# Rocky_Switch_SSR.net
KiCad netlist of a schematic drawn in EAGLE
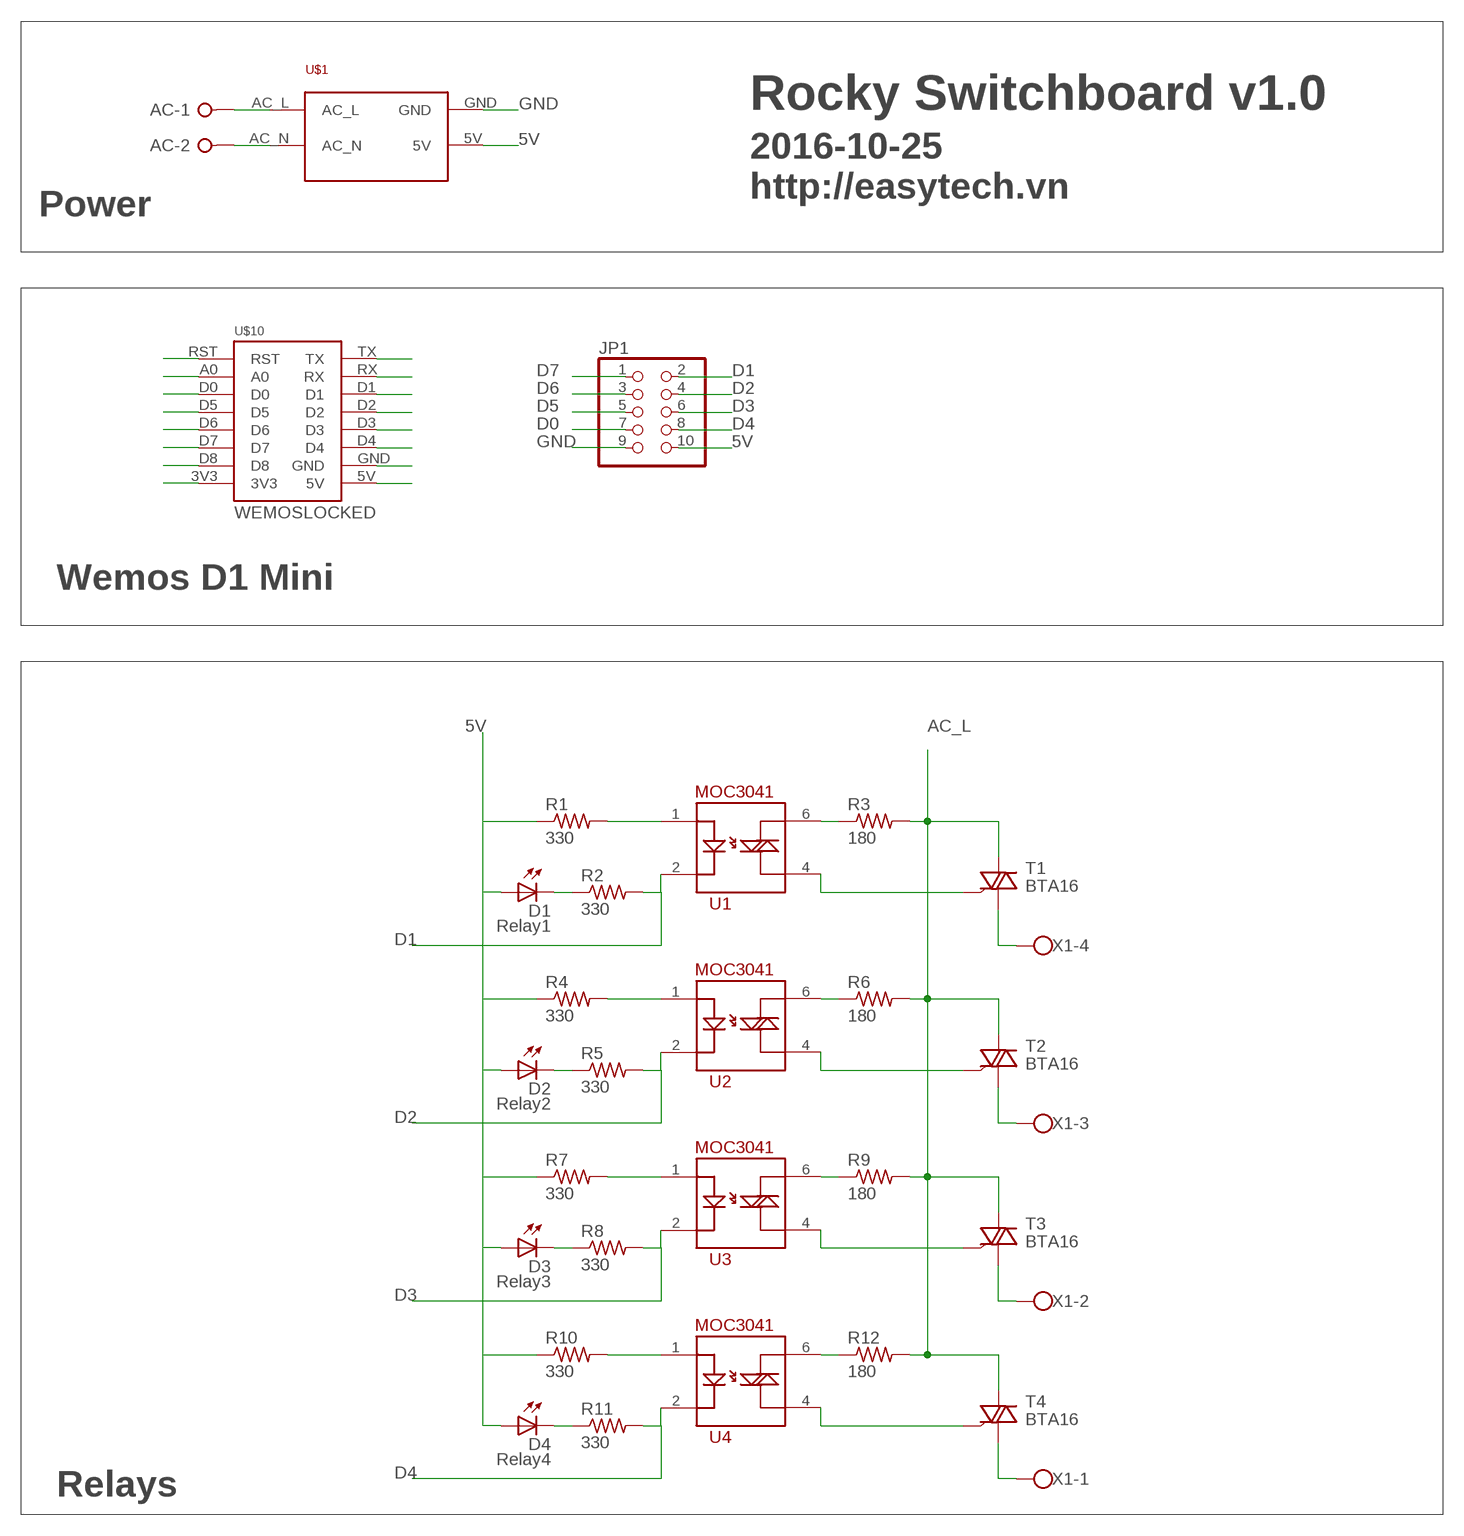
[diagram p0: schematic, sheet 1]

(export (version "E")
  (design (tool "Eeschema 10.0.6"))
  (components
    (comp (ref "AC")
      (value "W237-02P")
      (footprint "eagle-import:W237-132")
      (libsource (lib "eagle-import") (part "W237-02P"))
    )
    (comp (ref "D1")
      (value "Relay1")
      (footprint "eagle-import:CHIP-LED0805")
      (libsource (lib "eagle-import") (part "LEDCHIP-LED0805"))
    )
    (comp (ref "D2")
      (value "Relay2")
      (footprint "eagle-import:CHIP-LED0805")
      (libsource (lib "eagle-import") (part "LEDCHIP-LED0805"))
    )
    (comp (ref "D3")
      (value "Relay3")
      (footprint "eagle-import:CHIP-LED0805")
      (libsource (lib "eagle-import") (part "LEDCHIP-LED0805"))
    )
    (comp (ref "D4")
      (value "Relay4")
      (footprint "eagle-import:CHIP-LED0805")
      (libsource (lib "eagle-import") (part "LEDCHIP-LED0805"))
    )
    (comp (ref "JP1")
      (value "PINHD-2X5")
      (footprint "eagle-import:2X05")
      (libsource (lib "eagle-import") (part "PINHD-2X5"))
    )
    (comp (ref "R1")
      (value "330")
      (footprint "eagle-import:R0805")
      (libsource (lib "eagle-import") (part "R-US_R0805"))
    )
    (comp (ref "R2")
      (value "330")
      (footprint "eagle-import:R0805")
      (libsource (lib "eagle-import") (part "R-US_R0805"))
    )
    (comp (ref "R3")
      (value "180")
      (footprint "eagle-import:0204_7")
      (libsource (lib "eagle-import") (part "R-US_0204/7"))
    )
    (comp (ref "R4")
      (value "330")
      (footprint "eagle-import:R0805")
      (libsource (lib "eagle-import") (part "R-US_R0805"))
    )
    (comp (ref "R5")
      (value "330")
      (footprint "eagle-import:R0805")
      (libsource (lib "eagle-import") (part "R-US_R0805"))
    )
    (comp (ref "R6")
      (value "180")
      (footprint "eagle-import:0204_7")
      (libsource (lib "eagle-import") (part "R-US_0204/7"))
    )
    (comp (ref "R7")
      (value "330")
      (footprint "eagle-import:R0805")
      (libsource (lib "eagle-import") (part "R-US_R0805"))
    )
    (comp (ref "R8")
      (value "330")
      (footprint "eagle-import:R0805")
      (libsource (lib "eagle-import") (part "R-US_R0805"))
    )
    (comp (ref "R9")
      (value "180")
      (footprint "eagle-import:0204_7")
      (libsource (lib "eagle-import") (part "R-US_0204/7"))
    )
    (comp (ref "R10")
      (value "330")
      (footprint "eagle-import:R0805")
      (libsource (lib "eagle-import") (part "R-US_R0805"))
    )
    (comp (ref "R11")
      (value "330")
      (footprint "eagle-import:R0805")
      (libsource (lib "eagle-import") (part "R-US_R0805"))
    )
    (comp (ref "R12")
      (value "180")
      (footprint "eagle-import:0204_7")
      (libsource (lib "eagle-import") (part "R-US_0204/7"))
    )
    (comp (ref "T1")
      (value "BTA16")
      (footprint "eagle-import:TO220BV")
      (libsource (lib "eagle-import") (part "BT138-V"))
    )
    (comp (ref "T2")
      (value "BTA16")
      (footprint "eagle-import:TO220BV")
      (libsource (lib "eagle-import") (part "BT138-V"))
    )
    (comp (ref "T3")
      (value "BTA16")
      (footprint "eagle-import:TO220BV")
      (libsource (lib "eagle-import") (part "BT138-V"))
    )
    (comp (ref "T4")
      (value "BTA16")
      (footprint "eagle-import:TO220BV")
      (libsource (lib "eagle-import") (part "BT138-V"))
    )
    (comp (ref "U$1")
      (value "POWER_SUPPLY_220VAC_5V")
      (footprint "eagle-import:POWER_SUPPLY_220VAC_5V")
      (libsource (lib "eagle-import") (part "POWER_SUPPLY_220VAC_5V"))
    )
    (comp (ref "U$10")
      (value "WEMOSLOCKED")
      (footprint "eagle-import:WEMOS_LOCKED")
      (libsource (lib "eagle-import") (part "WEMOSLOCKED"))
    )
    (comp (ref "U1")
      (value "MOC3041")
      (footprint "eagle-import:DIL06")
      (libsource (lib "eagle-import") (part "MOC3031-M"))
    )
    (comp (ref "U2")
      (value "MOC3041")
      (footprint "eagle-import:DIL06")
      (libsource (lib "eagle-import") (part "MOC3031-M"))
    )
    (comp (ref "U3")
      (value "MOC3041")
      (footprint "eagle-import:DIL06")
      (libsource (lib "eagle-import") (part "MOC3031-M"))
    )
    (comp (ref "U4")
      (value "MOC3041")
      (footprint "eagle-import:DIL06")
      (libsource (lib "eagle-import") (part "MOC3031-M"))
    )
    (comp (ref "X1")
      (value "W237-4")
      (footprint "eagle-import:W237-4")
      (libsource (lib "eagle-import") (part "W237-4"))
    )
  )
  (nets
    (net (code "1") (name "/5V") (class "Default")
      (node (ref "D1") (pin "A") (pinfunction "A_A") (pintype "passive"))
      (node (ref "D2") (pin "A") (pinfunction "A_A") (pintype "passive"))
      (node (ref "D3") (pin "A") (pinfunction "A_A") (pintype "passive"))
      (node (ref "D4") (pin "A") (pinfunction "A_A") (pintype "passive"))
      (node (ref "JP1") (pin "10") (pinfunction "10_10") (pintype "passive"))
      (node (ref "R1") (pin "1") (pinfunction "1_1") (pintype "passive"))
      (node (ref "R10") (pin "1") (pinfunction "1_1") (pintype "passive"))
      (node (ref "R4") (pin "1") (pinfunction "1_1") (pintype "passive"))
      (node (ref "R7") (pin "1") (pinfunction "1_1") (pintype "passive"))
      (node (ref "U$1") (pin "5V") (pinfunction "5V_5V") (pintype "bidirectional"))
      (node (ref "U$10") (pin "5V") (pinfunction "5V_5V") (pintype "bidirectional"))
    )
    (net (code "2") (name "/AC_L") (class "Default")
      (node (ref "AC") (pin "1") (pinfunction "KL_1") (pintype "passive"))
      (node (ref "R12") (pin "2") (pinfunction "2_2") (pintype "passive"))
      (node (ref "R3") (pin "2") (pinfunction "2_2") (pintype "passive"))
      (node (ref "R6") (pin "2") (pinfunction "2_2") (pintype "passive"))
      (node (ref "R9") (pin "2") (pinfunction "2_2") (pintype "passive"))
      (node (ref "T1") (pin "T2") (pinfunction "A2_T2") (pintype "passive"))
      (node (ref "T2") (pin "T2") (pinfunction "A2_T2") (pintype "passive"))
      (node (ref "T3") (pin "T2") (pinfunction "A2_T2") (pintype "passive"))
      (node (ref "T4") (pin "T2") (pinfunction "A2_T2") (pintype "passive"))
      (node (ref "U$1") (pin "AC_L") (pinfunction "AC_L_AC_L") (pintype "bidirectional"))
    )
    (net (code "3") (name "/D0") (class "Default")
      (node (ref "JP1") (pin "7") (pinfunction "7_7") (pintype "passive"))
      (node (ref "U$10") (pin "D0") (pinfunction "D0_D0") (pintype "bidirectional"))
    )
    (net (code "4") (name "/D1") (class "Default")
      (node (ref "JP1") (pin "2") (pinfunction "2_2") (pintype "passive"))
      (node (ref "R2") (pin "2") (pinfunction "2_2") (pintype "passive"))
      (node (ref "U$10") (pin "D1") (pinfunction "D1_D1") (pintype "bidirectional"))
      (node (ref "U1") (pin "2") (pinfunction "2_2") (pintype "bidirectional"))
    )
    (net (code "5") (name "/D2") (class "Default")
      (node (ref "JP1") (pin "4") (pinfunction "4_4") (pintype "passive"))
      (node (ref "R5") (pin "2") (pinfunction "2_2") (pintype "passive"))
      (node (ref "U$10") (pin "D2") (pinfunction "D2_D2") (pintype "bidirectional"))
      (node (ref "U2") (pin "2") (pinfunction "2_2") (pintype "bidirectional"))
    )
    (net (code "6") (name "/D3") (class "Default")
      (node (ref "JP1") (pin "6") (pinfunction "6_6") (pintype "passive"))
      (node (ref "R8") (pin "2") (pinfunction "2_2") (pintype "passive"))
      (node (ref "U$10") (pin "D3") (pinfunction "D3_D3") (pintype "bidirectional"))
      (node (ref "U3") (pin "2") (pinfunction "2_2") (pintype "bidirectional"))
    )
    (net (code "7") (name "/D4") (class "Default")
      (node (ref "JP1") (pin "8") (pinfunction "8_8") (pintype "passive"))
      (node (ref "R11") (pin "2") (pinfunction "2_2") (pintype "passive"))
      (node (ref "U$10") (pin "D4") (pinfunction "D4_D4") (pintype "bidirectional"))
      (node (ref "U4") (pin "2") (pinfunction "2_2") (pintype "bidirectional"))
    )
    (net (code "8") (name "/D5") (class "Default")
      (node (ref "JP1") (pin "5") (pinfunction "5_5") (pintype "passive"))
      (node (ref "U$10") (pin "D5") (pinfunction "D5_D5") (pintype "bidirectional"))
    )
    (net (code "9") (name "/D6") (class "Default")
      (node (ref "JP1") (pin "3") (pinfunction "3_3") (pintype "passive"))
      (node (ref "U$10") (pin "D6") (pinfunction "D6_D6") (pintype "bidirectional"))
    )
    (net (code "10") (name "/D7") (class "Default")
      (node (ref "JP1") (pin "1") (pinfunction "1_1") (pintype "passive"))
      (node (ref "U$10") (pin "D7") (pinfunction "D7_D7") (pintype "bidirectional"))
    )
    (net (code "11") (name "/GND") (class "Default")
      (node (ref "JP1") (pin "9") (pinfunction "9_9") (pintype "passive"))
      (node (ref "U$1") (pin "GND") (pinfunction "GND_GND") (pintype "bidirectional"))
      (node (ref "U$10") (pin "GND") (pinfunction "GND_GND") (pintype "bidirectional"))
    )
    (net (code "12") (name "Net-(ACB-KL)") (class "Default")
      (node (ref "AC") (pin "2") (pinfunction "KL_2") (pintype "passive"))
      (node (ref "U$1") (pin "AC_N") (pinfunction "AC_N_AC_N") (pintype "bidirectional"))
    )
    (net (code "13") (name "Net-(D1-PadC)") (class "Default")
      (node (ref "D1") (pin "C") (pinfunction "C_C") (pintype "passive"))
      (node (ref "R2") (pin "1") (pinfunction "1_1") (pintype "passive"))
    )
    (net (code "14") (name "Net-(D2-PadC)") (class "Default")
      (node (ref "D2") (pin "C") (pinfunction "C_C") (pintype "passive"))
      (node (ref "R5") (pin "1") (pinfunction "1_1") (pintype "passive"))
    )
    (net (code "15") (name "Net-(D3-PadC)") (class "Default")
      (node (ref "D3") (pin "C") (pinfunction "C_C") (pintype "passive"))
      (node (ref "R8") (pin "1") (pinfunction "1_1") (pintype "passive"))
    )
    (net (code "16") (name "Net-(D4-PadC)") (class "Default")
      (node (ref "D4") (pin "C") (pinfunction "C_C") (pintype "passive"))
      (node (ref "R11") (pin "1") (pinfunction "1_1") (pintype "passive"))
    )
    (net (code "17") (name "Net-(R1-Pad2)") (class "Default")
      (node (ref "R1") (pin "2") (pinfunction "2_2") (pintype "passive"))
      (node (ref "U1") (pin "1") (pinfunction "1_1") (pintype "bidirectional"))
    )
    (net (code "18") (name "Net-(R3-Pad1)") (class "Default")
      (node (ref "R3") (pin "1") (pinfunction "1_1") (pintype "passive"))
      (node (ref "U1") (pin "6") (pinfunction "6_6") (pintype "bidirectional"))
    )
    (net (code "19") (name "Net-(R4-Pad2)") (class "Default")
      (node (ref "R4") (pin "2") (pinfunction "2_2") (pintype "passive"))
      (node (ref "U2") (pin "1") (pinfunction "1_1") (pintype "bidirectional"))
    )
    (net (code "20") (name "Net-(R6-Pad1)") (class "Default")
      (node (ref "R6") (pin "1") (pinfunction "1_1") (pintype "passive"))
      (node (ref "U2") (pin "6") (pinfunction "6_6") (pintype "bidirectional"))
    )
    (net (code "21") (name "Net-(R7-Pad2)") (class "Default")
      (node (ref "R7") (pin "2") (pinfunction "2_2") (pintype "passive"))
      (node (ref "U3") (pin "1") (pinfunction "1_1") (pintype "bidirectional"))
    )
    (net (code "22") (name "Net-(R9-Pad1)") (class "Default")
      (node (ref "R9") (pin "1") (pinfunction "1_1") (pintype "passive"))
      (node (ref "U3") (pin "6") (pinfunction "6_6") (pintype "bidirectional"))
    )
    (net (code "23") (name "Net-(R10-Pad2)") (class "Default")
      (node (ref "R10") (pin "2") (pinfunction "2_2") (pintype "passive"))
      (node (ref "U4") (pin "1") (pinfunction "1_1") (pintype "bidirectional"))
    )
    (net (code "24") (name "Net-(R12-Pad1)") (class "Default")
      (node (ref "R12") (pin "1") (pinfunction "1_1") (pintype "passive"))
      (node (ref "U4") (pin "6") (pinfunction "6_6") (pintype "bidirectional"))
    )
    (net (code "25") (name "Net-(T1-A1)") (class "Default")
      (node (ref "T1") (pin "T1") (pinfunction "A1_T1") (pintype "passive"))
      (node (ref "X1") (pin "4") (pinfunction "KL_4") (pintype "passive"))
    )
    (net (code "26") (name "Net-(T1-PadG)") (class "Default")
      (node (ref "T1") (pin "G") (pinfunction "G_G") (pintype "passive"))
      (node (ref "U1") (pin "4") (pinfunction "4_4") (pintype "bidirectional"))
    )
    (net (code "27") (name "Net-(T2-A1)") (class "Default")
      (node (ref "T2") (pin "T1") (pinfunction "A1_T1") (pintype "passive"))
      (node (ref "X1") (pin "3") (pinfunction "KL_3") (pintype "passive"))
    )
    (net (code "28") (name "Net-(T2-PadG)") (class "Default")
      (node (ref "T2") (pin "G") (pinfunction "G_G") (pintype "passive"))
      (node (ref "U2") (pin "4") (pinfunction "4_4") (pintype "bidirectional"))
    )
    (net (code "29") (name "Net-(T3-A1)") (class "Default")
      (node (ref "T3") (pin "T1") (pinfunction "A1_T1") (pintype "passive"))
      (node (ref "X1") (pin "2") (pinfunction "KL_2") (pintype "passive"))
    )
    (net (code "30") (name "Net-(T3-PadG)") (class "Default")
      (node (ref "T3") (pin "G") (pinfunction "G_G") (pintype "passive"))
      (node (ref "U3") (pin "4") (pinfunction "4_4") (pintype "bidirectional"))
    )
    (net (code "31") (name "Net-(T4-A1)") (class "Default")
      (node (ref "T4") (pin "T1") (pinfunction "A1_T1") (pintype "passive"))
      (node (ref "X1") (pin "1") (pinfunction "KL_1") (pintype "passive"))
    )
    (net (code "32") (name "Net-(T4-PadG)") (class "Default")
      (node (ref "T4") (pin "G") (pinfunction "G_G") (pintype "passive"))
      (node (ref "U4") (pin "4") (pinfunction "4_4") (pintype "bidirectional"))
    )
    (net (code "33") (name "unconnected-(U$10-Pad3V3)") (class "Default")
      (node (ref "U$10") (pin "3V3") (pinfunction "3V3_3V3") (pintype "bidirectional"))
    )
    (net (code "34") (name "unconnected-(U$10-PadA0)") (class "Default")
      (node (ref "U$10") (pin "A0") (pinfunction "A0_A0") (pintype "bidirectional"))
    )
    (net (code "35") (name "unconnected-(U$10-PadD8)") (class "Default")
      (node (ref "U$10") (pin "D8") (pinfunction "D8_D8") (pintype "bidirectional"))
    )
    (net (code "36") (name "unconnected-(U$10-PadRST)") (class "Default")
      (node (ref "U$10") (pin "RST") (pinfunction "RST_RST") (pintype "bidirectional"))
    )
    (net (code "37") (name "unconnected-(U$10-PadRX)") (class "Default")
      (node (ref "U$10") (pin "RX") (pinfunction "RX_RX") (pintype "bidirectional"))
    )
    (net (code "38") (name "unconnected-(U$10-PadTX)") (class "Default")
      (node (ref "U$10") (pin "TX") (pinfunction "TX_TX") (pintype "bidirectional"))
    )
  )
)
